# 07-AD9546_Outputs.net
KiCad netlist of a schematic drawn in Altium Designer
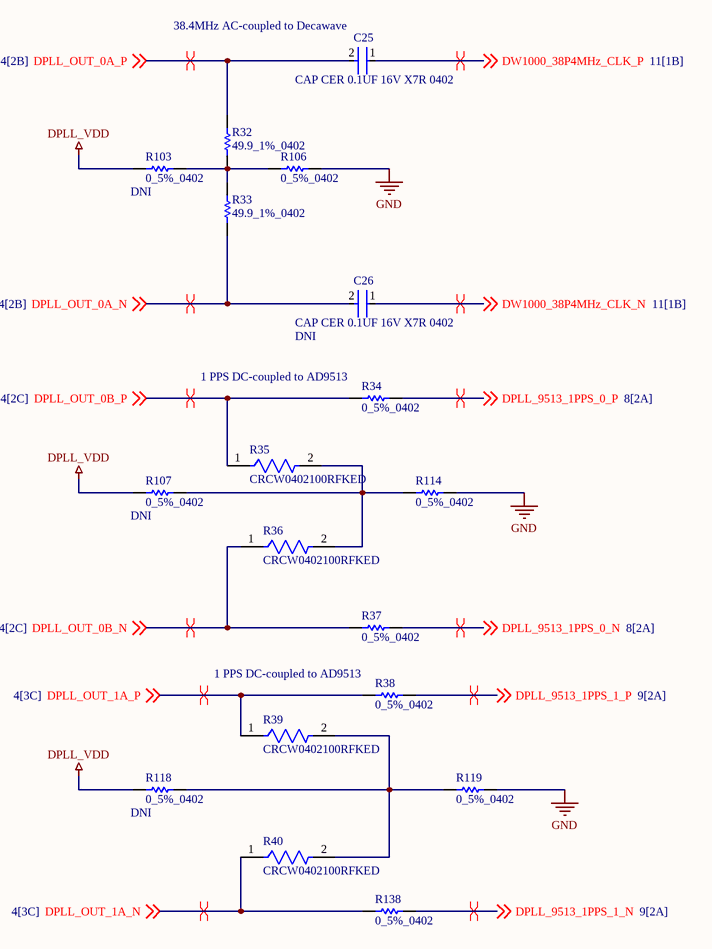
[diagram p0: 07-AD9546_Outputs.SchDoc]

(export (version "E")
  (design (tool "Eeschema 10.0.6"))
  (components
    (comp (ref "C25")
      (value "GRM155R71C104KA88D")
      (footprint "FP-GRM15-MFG")
      (description "CAP CER 0.1UF 16V X7R 0402")
      (fields
        (field (name "TOLERANCE") "10%")
        (field (name "OCTOPART") "https://octopart.com/grm155r71c104ka88d-murata-196880")
        (field (name "DIGIKEY DESCRIPTION") "CAP CER 0.1UF 16V X7R 0402")
      )
      (libsource (lib "Altium Content Vault") (part "236180d848d6139a670b325ea6854c9"))
    )
    (comp (ref "C26")
      (value "GRM155R71C104KA88D")
      (footprint "FP-GRM15-MFG")
      (description "CAP CER 0.1UF 16V X7R 0402")
      (fields
        (field (name "TOLERANCE") "10%")
        (field (name "OCTOPART") "https://octopart.com/grm155r71c104ka88d-murata-196880")
        (field (name "DIGIKEY DESCRIPTION") "CAP CER 0.1UF 16V X7R 0402")
        (field (name "DNI") "DNI")
      )
      (libsource (lib "Altium Content Vault") (part "236180d848d6139a670b325ea6854c9"))
    )
    (comp (ref "R32")
      (value "49.9_1%_0402")
      (footprint "RESC1005X40X25NL05T05")
      (fields (field (name "MANUFACTURER") "Panasonic") (field (name "PART NUMBER") "ERJ-2RKF49R9X"))
      (libsource (lib "Altium Content Vault") (part "RES"))
    )
    (comp (ref "R33")
      (value "49.9_1%_0402")
      (footprint "RESC1005X40X25NL05T05")
      (fields (field (name "MANUFACTURER") "Panasonic") (field (name "PART NUMBER") "ERJ-2RKF49R9X"))
      (libsource (lib "Altium Content Vault") (part "RES"))
    )
    (comp (ref "R34")
      (value "0_5%_0402")
      (footprint "RESC1005X40X25LL10T10")
      (fields (field (name "MANUFACTURER") "KOA Speer") (field (name "PART NUMBER") "RK73Z1ETTP"))
      (libsource (lib "Altium Content Vault") (part "RES"))
    )
    (comp (ref "R35")
      (value "CRCW0402100RFKED")
      (footprint "FP-CRCW0402-e3-IPC_C")
      (description "RES Thick Film, 100Ω, 1%, 0.063W, 100ppm/°C, 0402")
      (fields (field (name "TOLERANCE") "1%"))
      (libsource (lib "Altium Content Vault") (part "1029c3af85768c4190bb7ad29bc67b5"))
    )
    (comp (ref "R36")
      (value "CRCW0402100RFKED")
      (footprint "FP-CRCW0402-e3-IPC_C")
      (description "RES Thick Film, 100Ω, 1%, 0.063W, 100ppm/°C, 0402")
      (fields (field (name "TOLERANCE") "1%"))
      (libsource (lib "Altium Content Vault") (part "1029c3af85768c4190bb7ad29bc67b5"))
    )
    (comp (ref "R37")
      (value "0_5%_0402")
      (footprint "RESC1005X40X25LL10T10")
      (fields (field (name "MANUFACTURER") "KOA Speer") (field (name "PART NUMBER") "RK73Z1ETTP"))
      (libsource (lib "Altium Content Vault") (part "RES"))
    )
    (comp (ref "R38")
      (value "0_5%_0402")
      (footprint "RESC1005X40X25LL10T10")
      (fields (field (name "MANUFACTURER") "KOA Speer") (field (name "PART NUMBER") "RK73Z1ETTP"))
      (libsource (lib "Altium Content Vault") (part "RES"))
    )
    (comp (ref "R39")
      (value "CRCW0402100RFKED")
      (footprint "FP-CRCW0402-e3-IPC_C")
      (description "RES Thick Film, 100Ω, 1%, 0.063W, 100ppm/°C, 0402")
      (fields (field (name "TOLERANCE") "1%"))
      (libsource (lib "Altium Content Vault") (part "1029c3af85768c4190bb7ad29bc67b5"))
    )
    (comp (ref "R40")
      (value "CRCW0402100RFKED")
      (footprint "FP-CRCW0402-e3-IPC_C")
      (description "RES Thick Film, 100Ω, 1%, 0.063W, 100ppm/°C, 0402")
      (fields (field (name "TOLERANCE") "1%"))
      (libsource (lib "Altium Content Vault") (part "1029c3af85768c4190bb7ad29bc67b5"))
    )
    (comp (ref "R103")
      (value "0_5%_0402")
      (footprint "RESC1005X40X25LL10T10")
      (fields
        (field (name "MANUFACTURER") "KOA Speer")
        (field (name "PART NUMBER") "RK73Z1ETTP")
        (field (name "DNI") "DNI")
      )
      (libsource (lib "Altium Content Vault") (part "RES"))
    )
    (comp (ref "R106")
      (value "0_5%_0402")
      (footprint "RESC1005X40X25LL10T10")
      (fields (field (name "MANUFACTURER") "KOA Speer") (field (name "PART NUMBER") "RK73Z1ETTP"))
      (libsource (lib "Altium Content Vault") (part "RES"))
    )
    (comp (ref "R107")
      (value "0_5%_0402")
      (footprint "RESC1005X40X25LL10T10")
      (fields
        (field (name "MANUFACTURER") "KOA Speer")
        (field (name "PART NUMBER") "RK73Z1ETTP")
        (field (name "DNI") "DNI")
      )
      (libsource (lib "Altium Content Vault") (part "RES"))
    )
    (comp (ref "R114")
      (value "0_5%_0402")
      (footprint "RESC1005X40X25LL10T10")
      (fields (field (name "MANUFACTURER") "KOA Speer") (field (name "PART NUMBER") "RK73Z1ETTP"))
      (libsource (lib "Altium Content Vault") (part "RES"))
    )
    (comp (ref "R118")
      (value "0_5%_0402")
      (footprint "RESC1005X40X25LL10T10")
      (fields
        (field (name "MANUFACTURER") "KOA Speer")
        (field (name "PART NUMBER") "RK73Z1ETTP")
        (field (name "DNI") "DNI")
      )
      (libsource (lib "Altium Content Vault") (part "RES"))
    )
    (comp (ref "R119")
      (value "0_5%_0402")
      (footprint "RESC1005X40X25LL10T10")
      (fields (field (name "MANUFACTURER") "KOA Speer") (field (name "PART NUMBER") "RK73Z1ETTP"))
      (libsource (lib "Altium Content Vault") (part "RES"))
    )
    (comp (ref "R138")
      (value "0_5%_0402")
      (footprint "RESC1005X40X25LL10T10")
      (fields (field (name "MANUFACTURER") "KOA Speer") (field (name "PART NUMBER") "RK73Z1ETTP"))
      (libsource (lib "Altium Content Vault") (part "RES"))
    )
  )
  (nets
    (net (code "1") (name "DPLL_9513_1PPS_0_N") (class "Default")
      (node (ref "R37") (pin "2") (pinfunction "2_2") (pintype "passive"))
    )
    (net (code "2") (name "DPLL_9513_1PPS_0_P") (class "Default")
      (node (ref "R34") (pin "2") (pinfunction "2_2") (pintype "passive"))
    )
    (net (code "3") (name "DPLL_9513_1PPS_1_N") (class "Default")
      (node (ref "R138") (pin "2") (pinfunction "2_2") (pintype "passive"))
    )
    (net (code "4") (name "DPLL_9513_1PPS_1_P") (class "Default")
      (node (ref "R38") (pin "2") (pinfunction "2_2") (pintype "passive"))
    )
    (net (code "5") (name "DPLL_OUT_0A_N") (class "Default")
      (node (ref "C26") (pin "2") (pinfunction "2_2") (pintype "passive"))
      (node (ref "R33") (pin "1") (pinfunction "1_1") (pintype "passive"))
    )
    (net (code "6") (name "DPLL_OUT_0A_P") (class "Default")
      (node (ref "C25") (pin "2") (pinfunction "2_2") (pintype "passive"))
      (node (ref "R32") (pin "2") (pinfunction "2_2") (pintype "passive"))
    )
    (net (code "7") (name "DPLL_OUT_0B_N") (class "Default")
      (node (ref "R36") (pin "1") (pinfunction "1_1") (pintype "passive"))
      (node (ref "R37") (pin "1") (pinfunction "1_1") (pintype "passive"))
    )
    (net (code "8") (name "DPLL_OUT_0B_P") (class "Default")
      (node (ref "R34") (pin "1") (pinfunction "1_1") (pintype "passive"))
      (node (ref "R35") (pin "1") (pinfunction "1_1") (pintype "passive"))
    )
    (net (code "9") (name "DPLL_OUT_1A_N") (class "Default")
      (node (ref "R138") (pin "1") (pinfunction "1_1") (pintype "passive"))
      (node (ref "R40") (pin "1") (pinfunction "1_1") (pintype "passive"))
    )
    (net (code "10") (name "DPLL_OUT_1A_P") (class "Default")
      (node (ref "R38") (pin "1") (pinfunction "1_1") (pintype "passive"))
      (node (ref "R39") (pin "1") (pinfunction "1_1") (pintype "passive"))
    )
    (net (code "11") (name "DPLL_VDD") (class "Default")
      (node (ref "R103") (pin "1") (pinfunction "1_1") (pintype "passive"))
      (node (ref "R107") (pin "1") (pinfunction "1_1") (pintype "passive"))
      (node (ref "R118") (pin "1") (pinfunction "1_1") (pintype "passive"))
    )
    (net (code "12") (name "DW1000_38P4MHz_CLK_N") (class "Default")
      (node (ref "C26") (pin "1") (pinfunction "1_1") (pintype "passive"))
    )
    (net (code "13") (name "DW1000_38P4MHz_CLK_P") (class "Default")
      (node (ref "C25") (pin "1") (pinfunction "1_1") (pintype "passive"))
    )
    (net (code "14") (name "GND") (class "Default")
      (node (ref "R106") (pin "2") (pinfunction "2_2") (pintype "passive"))
      (node (ref "R114") (pin "2") (pinfunction "2_2") (pintype "passive"))
      (node (ref "R119") (pin "2") (pinfunction "2_2") (pintype "passive"))
    )
    (net (code "15") (name "Net-(R103-Pad2)") (class "Default")
      (node (ref "R103") (pin "2") (pinfunction "2_2") (pintype "passive"))
      (node (ref "R106") (pin "1") (pinfunction "1_1") (pintype "passive"))
      (node (ref "R32") (pin "1") (pinfunction "1_1") (pintype "passive"))
      (node (ref "R33") (pin "2") (pinfunction "2_2") (pintype "passive"))
    )
    (net (code "16") (name "Net-(R107-Pad2)") (class "Default")
      (node (ref "R107") (pin "2") (pinfunction "2_2") (pintype "passive"))
      (node (ref "R114") (pin "1") (pinfunction "1_1") (pintype "passive"))
      (node (ref "R35") (pin "2") (pinfunction "2_2") (pintype "passive"))
      (node (ref "R36") (pin "2") (pinfunction "2_2") (pintype "passive"))
    )
    (net (code "17") (name "Net-(R118-Pad2)") (class "Default")
      (node (ref "R118") (pin "2") (pinfunction "2_2") (pintype "passive"))
      (node (ref "R119") (pin "1") (pinfunction "1_1") (pintype "passive"))
      (node (ref "R39") (pin "2") (pinfunction "2_2") (pintype "passive"))
      (node (ref "R40") (pin "2") (pinfunction "2_2") (pintype "passive"))
    )
  )
)
